# BMS_Slave_Device_R1_5.net
KiCad netlist of a schematic drawn in Altium Designer
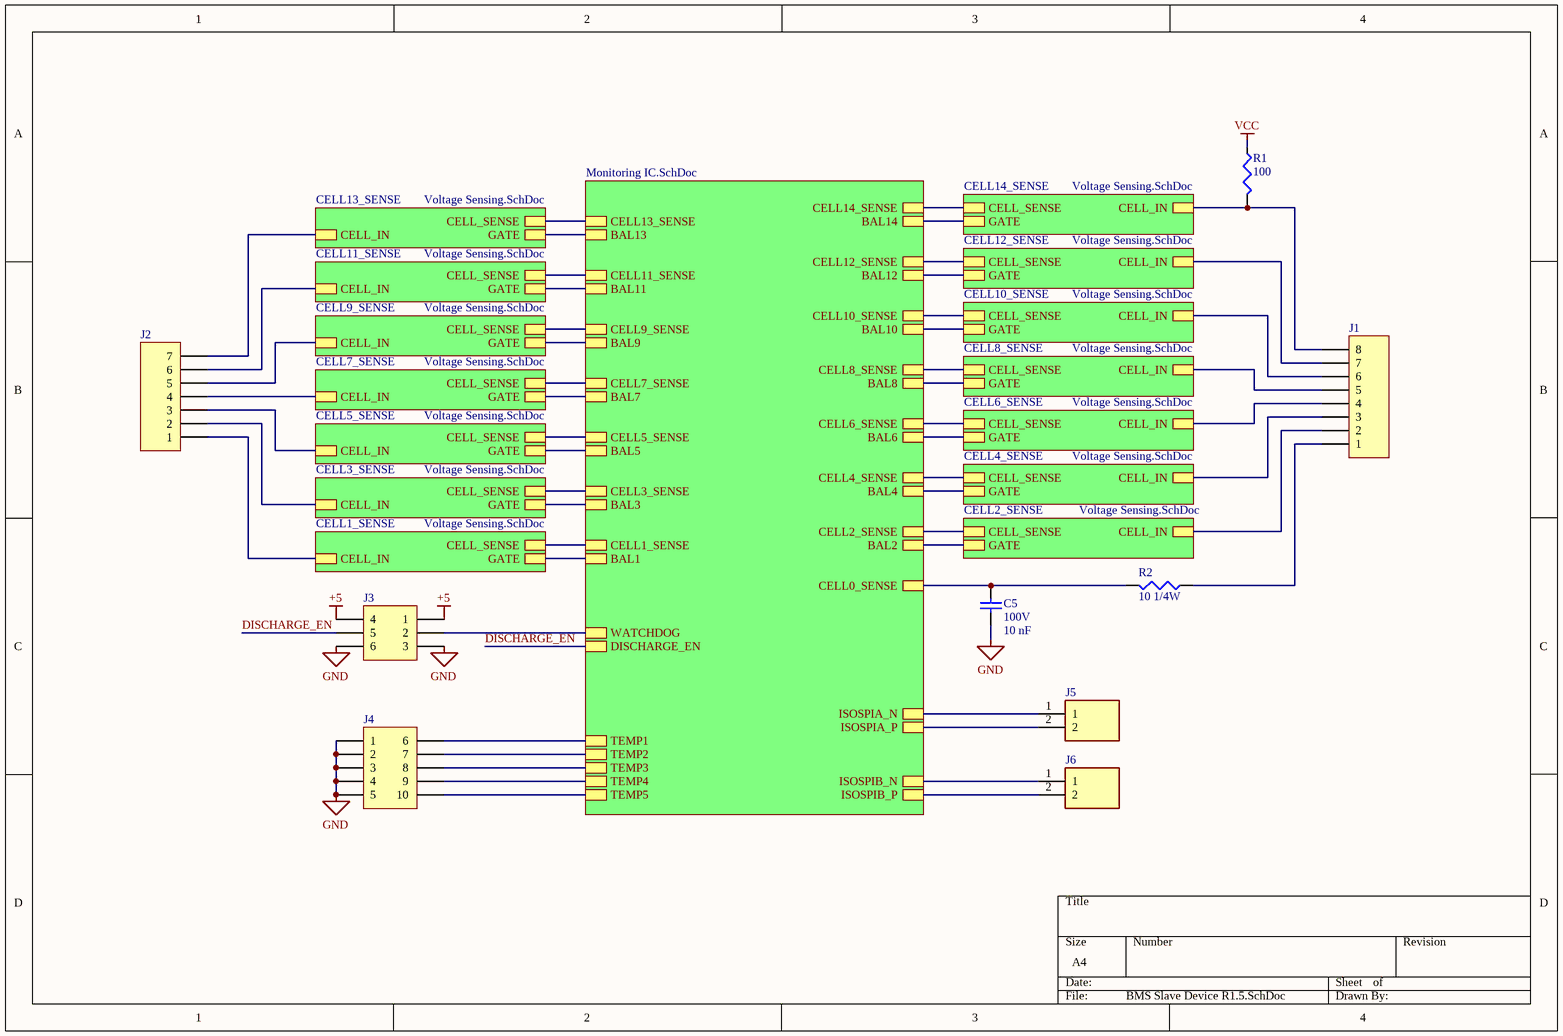
[diagram p0: BMS Slave Device R1.5.SchDoc]

(export (version "E")
  (design (tool "Eeschema 10.0.6"))
  (components
    (comp (ref "C5")
      (value "100V")
      (footprint "6-0805_N")
      (description "Capacitor")
      (fields (field (name "100V") "10 nF") (field (name "PUBLISHER") "Altium Limited"))
      (libsource (lib "Miscellaneous Devices") (part "Cap"))
    )
    (comp (ref "J1")
      (value "Header 8")
      (footprint "HDR1X8")
      (description "Header, 8-Pin")
      (fields (field (name "PUBLISHER") "Altium Limited"))
      (libsource (lib "Miscellaneous Connectors") (part "Header 8"))
    )
    (comp (ref "J2")
      (value "ODD CELLS")
      (footprint "HDR1X7")
      (fields (field (name "PUBLISHER") "Altium Limited"))
      (libsource (lib "Miscellaneous Connectors") (part "Header 7"))
    )
    (comp (ref "J3")
      (value "~")
      (footprint "HDR2X3_CEN")
      (description "Header, 3-Pin, Dual row")
      (fields (field (name "PUBLISHER") "Altium Limited"))
      (libsource (lib "Miscellaneous Connectors") (part "Header 3X2A"))
    )
    (comp (ref "J4")
      (value "THERMISTORS")
      (footprint "HDR2X5_CEN")
      (description "Header, 5-Pin, Dual row")
      (fields (field (name "PUBLISHER") "Altium Limited"))
      (libsource (lib "Miscellaneous Connectors") (part "Header 5X2A"))
    )
    (comp (ref "J5")
      (value "B2B-XH-2__LF__SN_")
      (footprint "BMS Slave Device R1:B2BXH2LFSN")
      (description "Connector")
      (fields
        (field (name "MANUFACTURER_PART_NUMBER") "B2B-XH-2 (LF)(SN)")
        (field (name "RS PART NUMBER") "1755499")
      )
      (libsource (lib "BMS Slave Device R1") (part "B2B-XH-2__LF__SN_"))
    )
    (comp (ref "J6")
      (value "B2B-XH-2__LF__SN_")
      (footprint "BMS Slave Device R1:B2BXH2LFSN")
      (description "Connector")
      (fields
        (field (name "MANUFACTURER_PART_NUMBER") "B2B-XH-2 (LF)(SN)")
        (field (name "RS PART NUMBER") "1755499")
      )
      (libsource (lib "BMS Slave Device R1") (part "B2B-XH-2__LF__SN_"))
    )
    (comp (ref "R1")
      (value "100")
      (footprint "J1-0603")
      (description "Resistor")
      (fields (field (name "Comment") "Res3") (field (name "PUBLISHER") "Altium Limited"))
      (libsource (lib "Miscellaneous Devices") (part "Res3"))
    )
    (comp (ref "R2")
      (value "10 1/4W")
      (footprint "C1206")
      (description "Resistor")
      (fields (field (name "PUBLISHER") "Altium Limited"))
      (libsource (lib "Miscellaneous Devices") (part "Res3"))
    )
  )
  (nets
    (net (code "1") (name "+5") (class "Default")
      (node (ref "J3") (pin "1") (pinfunction "1_1") (pintype "passive"))
      (node (ref "J3") (pin "4") (pinfunction "4_4") (pintype "passive"))
    )
    (net (code "16") (name "/CELL0_SENSE") (class "Default")
      (node (ref "C5") (pin "2") (pinfunction "2_2") (pintype "passive"))
      (node (ref "R2") (pin "1") (pinfunction "1_1") (pintype "passive"))
    )
    (net (code "31") (name "/CELL_IN") (class "Default")
      (node (ref "J1") (pin "7") (pinfunction "7_7") (pintype "passive"))
    )
    (net (code "32") (name "/CELL_IN_1") (class "Default")
      (node (ref "J2") (pin "7") (pinfunction "7_7") (pintype "passive"))
    )
    (net (code "33") (name "/CELL_IN_2") (class "Default")
      (node (ref "J2") (pin "6") (pinfunction "6_6") (pintype "passive"))
    )
    (net (code "34") (name "/CELL_IN_3") (class "Default")
      (node (ref "J2") (pin "1") (pinfunction "1_1") (pintype "passive"))
    )
    (net (code "35") (name "/CELL_IN_4") (class "Default")
      (node (ref "J2") (pin "2") (pinfunction "2_2") (pintype "passive"))
    )
    (net (code "36") (name "/CELL_IN_5") (class "Default")
      (node (ref "J2") (pin "3") (pinfunction "3_3") (pintype "passive"))
    )
    (net (code "37") (name "/CELL_IN_6") (class "Default")
      (node (ref "J2") (pin "4") (pinfunction "4_4") (pintype "passive"))
    )
    (net (code "38") (name "/CELL_IN_7") (class "Default")
      (node (ref "J2") (pin "5") (pinfunction "5_5") (pintype "passive"))
    )
    (net (code "39") (name "/CELL_IN_8") (class "Default")
      (node (ref "J1") (pin "6") (pinfunction "6_6") (pintype "passive"))
    )
    (net (code "40") (name "/CELL_IN_9") (class "Default")
      (node (ref "J1") (pin "5") (pinfunction "5_5") (pintype "passive"))
    )
    (net (code "41") (name "/CELL_IN_10") (class "Default")
      (node (ref "J1") (pin "4") (pinfunction "4_4") (pintype "passive"))
    )
    (net (code "42") (name "/CELL_IN_11") (class "Default")
      (node (ref "J1") (pin "3") (pinfunction "3_3") (pintype "passive"))
    )
    (net (code "43") (name "/CELL_IN_12") (class "Default")
      (node (ref "J1") (pin "2") (pinfunction "2_2") (pintype "passive"))
    )
    (net (code "44") (name "/CELL_IN_13") (class "Default")
      (node (ref "J1") (pin "8") (pinfunction "8_8") (pintype "passive"))
      (node (ref "R1") (pin "1") (pinfunction "1_1") (pintype "passive"))
    )
    (net (code "45") (name "/DISCHARGE_EN") (class "Default")
      (node (ref "J3") (pin "5") (pinfunction "5_5") (pintype "passive"))
    )
    (net (code "46") (name "/ISOSPIA_N") (class "Default")
      (node (ref "J5") (pin "1") (pinfunction "1_1") (pintype "passive"))
    )
    (net (code "47") (name "/ISOSPIA_P") (class "Default")
      (node (ref "J5") (pin "2") (pinfunction "2_2") (pintype "passive"))
    )
    (net (code "48") (name "/ISOSPIB_N") (class "Default")
      (node (ref "J6") (pin "1") (pinfunction "1_1") (pintype "passive"))
    )
    (net (code "49") (name "/ISOSPIB_P") (class "Default")
      (node (ref "J6") (pin "2") (pinfunction "2_2") (pintype "passive"))
    )
    (net (code "50") (name "/TEMP1") (class "Default")
      (node (ref "J4") (pin "6") (pinfunction "6_6") (pintype "passive"))
    )
    (net (code "51") (name "/TEMP2") (class "Default")
      (node (ref "J4") (pin "7") (pinfunction "7_7") (pintype "passive"))
    )
    (net (code "52") (name "/TEMP3") (class "Default")
      (node (ref "J4") (pin "8") (pinfunction "8_8") (pintype "passive"))
    )
    (net (code "53") (name "/TEMP4") (class "Default")
      (node (ref "J4") (pin "9") (pinfunction "9_9") (pintype "passive"))
    )
    (net (code "54") (name "/TEMP5") (class "Default")
      (node (ref "J4") (pin "10") (pinfunction "10_10") (pintype "passive"))
    )
    (net (code "55") (name "/WATCHDOG") (class "Default")
      (node (ref "J3") (pin "2") (pinfunction "2_2") (pintype "passive"))
    )
    (net (code "56") (name "GND") (class "Default")
      (node (ref "C5") (pin "1") (pinfunction "1_1") (pintype "passive"))
      (node (ref "J3") (pin "3") (pinfunction "3_3") (pintype "passive"))
      (node (ref "J3") (pin "6") (pinfunction "6_6") (pintype "passive"))
      (node (ref "J4") (pin "1") (pinfunction "1_1") (pintype "passive"))
      (node (ref "J4") (pin "2") (pinfunction "2_2") (pintype "passive"))
      (node (ref "J4") (pin "3") (pinfunction "3_3") (pintype "passive"))
      (node (ref "J4") (pin "4") (pinfunction "4_4") (pintype "passive"))
      (node (ref "J4") (pin "5") (pinfunction "5_5") (pintype "passive"))
    )
    (net (code "57") (name "Net-(J1-Pad1)") (class "Default")
      (node (ref "J1") (pin "1") (pinfunction "1_1") (pintype "passive"))
      (node (ref "R2") (pin "2") (pinfunction "2_2") (pintype "passive"))
    )
    (net (code "58") (name "VCC") (class "Default")
      (node (ref "R1") (pin "2") (pinfunction "2_2") (pintype "passive"))
    )
  )
)
